# 04_io.net
KiCad netlist of a schematic drawn in Altium Designer
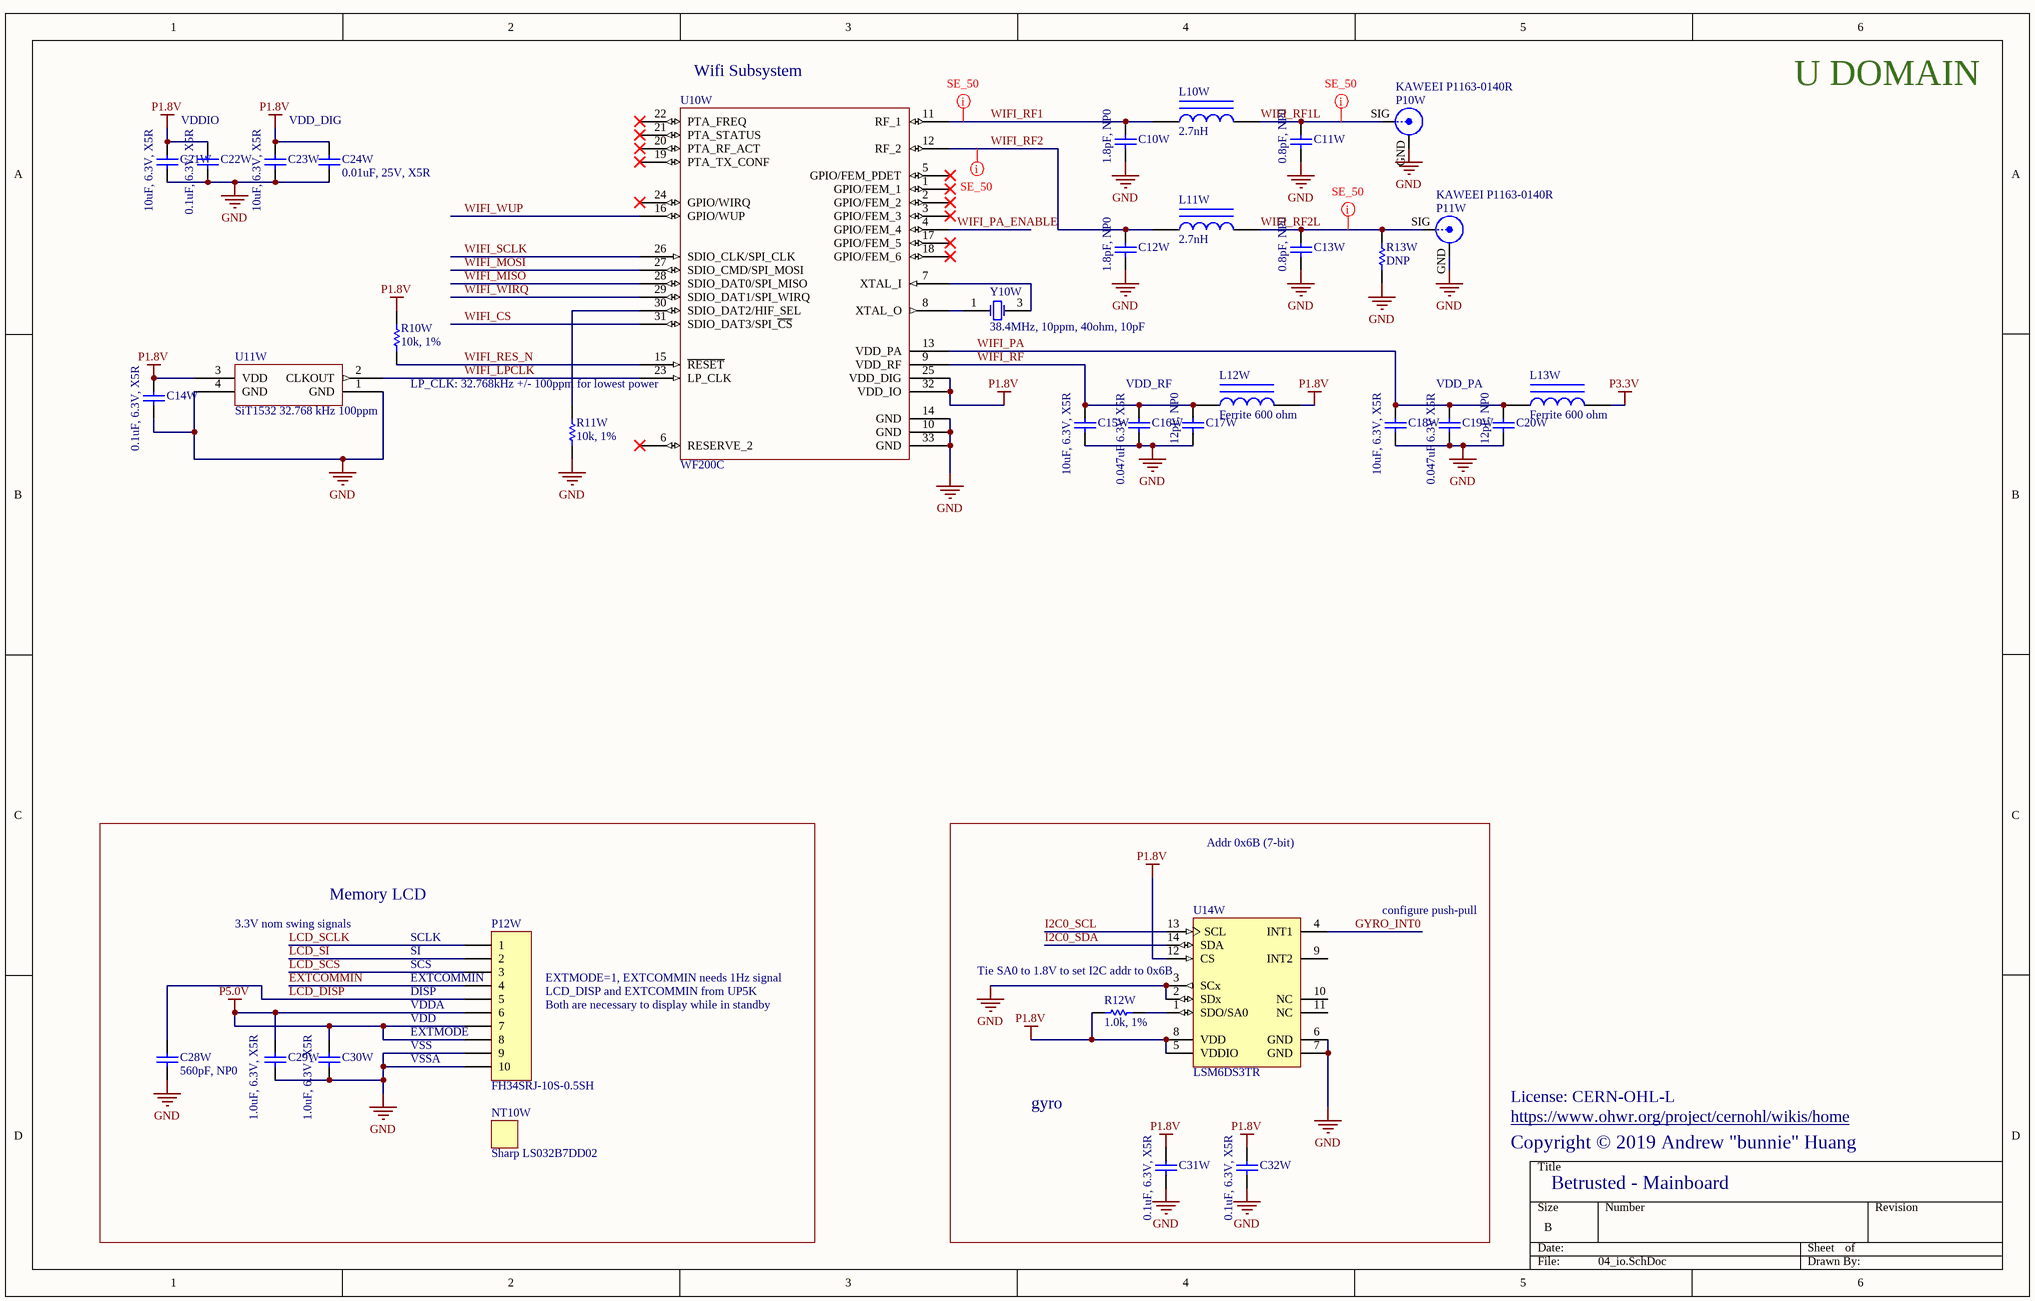
[diagram p0: 04_io.SchDoc]

(export (version "E")
  (design (tool "Eeschema 10.0.6"))
  (components
    (comp (ref "C10W")
      (value "1.8pF, NP0")
      (footprint "B_CAP0201")
      (description "Capacitor (Semiconductor SIM Model)")
      (fields (field (name "MPN") "GRM0335C1H1R8BA01D"))
      (libsource (lib "Miscellaneous Devices") (part "Cap Semi"))
    )
    (comp (ref "C11W")
      (value "0.8pF, NP0")
      (footprint "B_CAP0201")
      (description "Capacitor (Semiconductor SIM Model)")
      (fields (field (name "MPN") "GRM0335C1ER80BA01D"))
      (libsource (lib "Miscellaneous Devices") (part "Cap Semi"))
    )
    (comp (ref "C12W")
      (value "1.8pF, NP0")
      (footprint "B_CAP0201")
      (description "Capacitor (Semiconductor SIM Model)")
      (fields (field (name "MPN") "GRM0335C1H1R8BA01D"))
      (libsource (lib "Miscellaneous Devices") (part "Cap Semi"))
    )
    (comp (ref "C13W")
      (value "0.8pF, NP0")
      (footprint "B_CAP0201")
      (description "Capacitor (Semiconductor SIM Model)")
      (fields (field (name "MPN") "GRM0335C1ER80BA01D"))
      (libsource (lib "Miscellaneous Devices") (part "Cap Semi"))
    )
    (comp (ref "C14W")
      (value "0.1uF, 6.3V, X5R")
      (footprint "B_CAP0201")
      (description "Capacitor (Semiconductor SIM Model)")
      (fields (field (name "MPN") "CL03A104KQ3NNNC"))
      (libsource (lib "Miscellaneous Devices") (part "Cap Semi"))
    )
    (comp (ref "C15W")
      (value "10uF, 6.3V, X5R")
      (footprint "B_CAP0603")
      (description "Capacitor (Semiconductor SIM Model)")
      (fields (field (name "MPN") "CL10A106MQ8NNNC"))
      (libsource (lib "Miscellaneous Devices") (part "Cap Semi"))
    )
    (comp (ref "C16W")
      (value "0.047uF 6.3V X5R")
      (footprint "B_CAP0201")
      (description "Capacitor (Semiconductor SIM Model)")
      (fields (field (name "MPN") "CL03A473KQ3NNNC"))
      (libsource (lib "Miscellaneous Devices") (part "Cap Semi"))
    )
    (comp (ref "C17W")
      (value "12pF, NP0")
      (footprint "B_CAP0201")
      (description "Capacitor (Semiconductor SIM Model)")
      (fields (field (name "MPN") "GRM0335C1E120JA01D"))
      (libsource (lib "Miscellaneous Devices") (part "Cap Semi"))
    )
    (comp (ref "C18W")
      (value "10uF, 6.3V, X5R")
      (footprint "B_CAP0603")
      (description "Capacitor (Semiconductor SIM Model)")
      (fields (field (name "MPN") "CL10A106MQ8NNNC"))
      (libsource (lib "Miscellaneous Devices") (part "Cap Semi"))
    )
    (comp (ref "C19W")
      (value "0.047uF 6.3V X5R")
      (footprint "B_CAP0201")
      (description "Capacitor (Semiconductor SIM Model)")
      (fields (field (name "MPN") "CL03A473KQ3NNNC"))
      (libsource (lib "Miscellaneous Devices") (part "Cap Semi"))
    )
    (comp (ref "C20W")
      (value "12pF, NP0")
      (footprint "B_CAP0201")
      (description "Capacitor (Semiconductor SIM Model)")
      (fields (field (name "MPN") "GRM0335C1E120JA01D"))
      (libsource (lib "Miscellaneous Devices") (part "Cap Semi"))
    )
    (comp (ref "C21W")
      (value "10uF, 6.3V, X5R")
      (footprint "B_CAP0603")
      (description "Capacitor (Semiconductor SIM Model)")
      (fields (field (name "MPN") "CL10A106MQ8NNNC"))
      (libsource (lib "Miscellaneous Devices") (part "Cap Semi"))
    )
    (comp (ref "C22W")
      (value "0.1uF, 6.3V, X5R")
      (footprint "B_CAP0201")
      (description "Capacitor (Semiconductor SIM Model)")
      (fields (field (name "MPN") "CL03A104KQ3NNNC"))
      (libsource (lib "Miscellaneous Devices") (part "Cap Semi"))
    )
    (comp (ref "C23W")
      (value "10uF, 6.3V, X5R")
      (footprint "B_CAP0603")
      (description "Capacitor (Semiconductor SIM Model)")
      (fields (field (name "MPN") "CL10A106MQ8NNNC"))
      (libsource (lib "Miscellaneous Devices") (part "Cap Semi"))
    )
    (comp (ref "C24W")
      (value "0.01uF, 25V, X5R")
      (footprint "B_RES0201")
      (description "Capacitor (Semiconductor SIM Model)")
      (fields (field (name "MPN") "GRM033R61E103KA12D"))
      (libsource (lib "Miscellaneous Devices") (part "Cap Semi"))
    )
    (comp (ref "C28W")
      (value "560pF, NP0")
      (footprint "B_RES0201")
      (description "Capacitor (Semiconductor SIM Model)")
      (fields (field (name "MPN") "GRM0335C1E561JA01D"))
      (libsource (lib "Miscellaneous Devices") (part "Cap Semi"))
    )
    (comp (ref "C29W")
      (value "1.0uF, 6.3V, X5R")
      (footprint "B_CAP0201")
      (description "Capacitor (Semiconductor SIM Model)")
      (fields (field (name "MPN") "GRM033R60J105MEA2D"))
      (libsource (lib "Miscellaneous Devices") (part "Cap Semi"))
    )
    (comp (ref "C30W")
      (value "1.0uF, 6.3V, X5R")
      (footprint "B_CAP0201")
      (description "Capacitor (Semiconductor SIM Model)")
      (fields (field (name "MPN") "GRM033R60J105MEA2D"))
      (libsource (lib "Miscellaneous Devices") (part "Cap Semi"))
    )
    (comp (ref "C31W")
      (value "0.1uF, 6.3V, X5R")
      (footprint "B_CAP0201")
      (description "Capacitor (Semiconductor SIM Model)")
      (fields (field (name "MPN") "CL03A104KQ3NNNC"))
      (libsource (lib "Miscellaneous Devices") (part "Cap Semi"))
    )
    (comp (ref "C32W")
      (value "0.1uF, 6.3V, X5R")
      (footprint "B_CAP0201")
      (description "Capacitor (Semiconductor SIM Model)")
      (fields (field (name "MPN") "CL03A104KQ3NNNC"))
      (libsource (lib "Miscellaneous Devices") (part "Cap Semi"))
    )
    (comp (ref "L10W")
      (value "2.7nH")
      (footprint "B_IND0402")
      (description "Magnetic-Core Inductor")
      (fields (field (name "MPN") "LQW15AN2N7C00"))
      (libsource (lib "Miscellaneous Devices") (part "Inductor Iron"))
    )
    (comp (ref "L11W")
      (value "2.7nH")
      (footprint "B_IND0402")
      (description "Magnetic-Core Inductor")
      (fields (field (name "MPN") "LQW15AN2N7C00"))
      (libsource (lib "Miscellaneous Devices") (part "Inductor Iron"))
    )
    (comp (ref "L12W")
      (value "Ferrite 600 ohm")
      (footprint "B_IND0603")
      (description "Magnetic-Core Inductor")
      (fields (field (name "MPN") "BLM18AG601SN1D"))
      (libsource (lib "Miscellaneous Devices") (part "Inductor Iron"))
    )
    (comp (ref "L13W")
      (value "Ferrite 600 ohm")
      (footprint "B_IND0603")
      (description "Magnetic-Core Inductor")
      (fields (field (name "MPN") "BLM18AG601SN1D"))
      (libsource (lib "Miscellaneous Devices") (part "Inductor Iron"))
    )
    (comp (ref "NT10W")
      (value "Sharp LS032B7DD02")
      (description "Placeholder for non-board BOM items")
      (fields (field (name "MPN") "LS032B7DD02"))
      (libsource (lib "commonsch") (part "NOTE"))
    )
    (comp (ref "P10W")
      (value "KAWEEI P1163-0140R")
      (footprint "HRS_U.FL")
      (description "BNC Elbow Connector")
      (fields (field (name "MPN") "P1163-0140R") (field (name "PUBLISHER") "Altium Limited"))
      (libsource (lib "Miscellaneous Connectors") (part "BNC"))
    )
    (comp (ref "P11W")
      (value "KAWEEI P1163-0140R")
      (footprint "HRS_U.FL")
      (description "BNC Elbow Connector")
      (fields (field (name "MPN") "P1163-0140R") (field (name "PUBLISHER") "Altium Limited"))
      (libsource (lib "Miscellaneous Connectors") (part "BNC"))
    )
    (comp (ref "P12W")
      (value "FH34SRJ-10S-0.5SH")
      (footprint "HRS_FH34SRJ-10S-0.5SH(50)")
      (description "Header, 10-Pin")
      (fields (field (name "PUBLISHER") "Altium Limited"))
      (libsource (lib "Miscellaneous Connectors") (part "Header 10"))
    )
    (comp (ref "R10W")
      (value "10k, 1%")
      (footprint "B_RES0201")
      (description "Resistor")
      (fields (field (name "MPN") "ANY"))
      (libsource (lib "Miscellaneous Devices") (part "Res1"))
    )
    (comp (ref "R11W")
      (value "10k, 1%")
      (footprint "B_RES0201")
      (description "Resistor")
      (fields (field (name "MPN") "ANY"))
      (libsource (lib "Miscellaneous Devices") (part "Res1"))
    )
    (comp (ref "R12W")
      (value "1.0k, 1%")
      (footprint "B_RES0201")
      (description "Resistor")
      (fields (field (name "MPN") "ANY"))
      (libsource (lib "Miscellaneous Devices") (part "Res1"))
    )
    (comp (ref "R13W")
      (value "DNP")
      (footprint "B_RES0201")
      (description "Resistor")
      (libsource (lib "Miscellaneous Devices") (part "Res1"))
    )
    (comp (ref "U10W")
      (value "WF200C")
      (footprint "QFN40P400X400X90_HS-33N")
      (description "Wifi Network Coprocessor")
      (libsource (lib "commonsch-new") (part "WF200C(R)"))
    )
    (comp (ref "U11W")
      (value "SiT1532 32.768 kHz 100ppm")
      (footprint "SiTIME_CSP")
      (description "10ppm ultra low power 32.768 kHz replacement")
      (fields (field (name "MPN") "SIT1532AI-J4-DCC-32.768E"))
      (libsource (lib "altium-import") (part "root_2_SiT1532_"))
    )
    (comp (ref "U14W")
      (value "LSM6DS3TR")
      (footprint "LGA-14_2500X3000X860_N")
      (libsource (lib "commonsch-new") (part "LSM6DS3TR"))
    )
    (comp (ref "Y10W")
      (value "38.4MHz, 10ppm, 40ohm, 10pF")
      (footprint "XOSC_3.2_2.5")
      (description "Crystal Oscillator")
      (fields (field (name "MPN") "ECS-384-10-33B-CKY-TR") (field (name "PUBLISHER") "Altium Limited"))
      (libsource (lib "Miscellaneous Devices") (part "XTAL"))
    )
  )
  (nets
    (net (code "1") (name "/EXTCOMMIN") (class "Default")
      (node (ref "P12W") (pin "4") (pinfunction "4_4") (pintype "passive"))
    )
    (net (code "2") (name "/GYRO_INT0") (class "Default")
      (node (ref "U14W") (pin "4") (pinfunction "INT1_4") (pintype "open_collector"))
    )
    (net (code "3") (name "/I2C0_SCL") (class "Default")
      (node (ref "U14W") (pin "13") (pinfunction "SCL_13") (pintype "input"))
    )
    (net (code "4") (name "/I2C0_SDA") (class "Default")
      (node (ref "U14W") (pin "14") (pinfunction "SDA_14") (pintype "bidirectional"))
    )
    (net (code "5") (name "/LCD_DISP") (class "Default")
      (node (ref "C28W") (pin "1") (pinfunction "1_1") (pintype "passive"))
      (node (ref "P12W") (pin "5") (pinfunction "5_5") (pintype "passive"))
    )
    (net (code "6") (name "/LCD_SCLK") (class "Default")
      (node (ref "P12W") (pin "1") (pinfunction "1_1") (pintype "passive"))
    )
    (net (code "7") (name "/LCD_SCS") (class "Default")
      (node (ref "P12W") (pin "3") (pinfunction "3_3") (pintype "passive"))
    )
    (net (code "8") (name "/LCD_SI") (class "Default")
      (node (ref "P12W") (pin "2") (pinfunction "2_2") (pintype "passive"))
    )
    (net (code "9") (name "/WIFI_CS") (class "Default")
      (node (ref "U10W") (pin "31") (pinfunction "SDIO_DAT3/SPI_~{CS}_31") (pintype "bidirectional"))
    )
    (net (code "10") (name "/WIFI_LPCLK") (class "Default")
      (node (ref "U10W") (pin "23") (pinfunction "LP_CLK_23") (pintype "input"))
      (node (ref "U11W") (pin "2") (pinfunction "CLKOUT_2") (pintype "output"))
    )
    (net (code "11") (name "/WIFI_MISO") (class "Default")
      (node (ref "U10W") (pin "28") (pinfunction "SDIO_DAT0/SPI_MISO_28") (pintype "bidirectional"))
    )
    (net (code "12") (name "/WIFI_MOSI") (class "Default")
      (node (ref "U10W") (pin "27") (pinfunction "SDIO_CMD/SPI_MOSI_27") (pintype "bidirectional"))
    )
    (net (code "13") (name "/WIFI_PA") (class "Default")
      (node (ref "C18W") (pin "1") (pinfunction "1_1") (pintype "passive"))
      (node (ref "C19W") (pin "1") (pinfunction "1_1") (pintype "passive"))
      (node (ref "C20W") (pin "1") (pinfunction "1_1") (pintype "passive"))
      (node (ref "L13W") (pin "1") (pinfunction "1_1") (pintype "passive"))
      (node (ref "U10W") (pin "13") (pinfunction "VDD_PA_13") (pintype "power_in"))
    )
    (net (code "14") (name "/WIFI_PA_ENABLE") (class "Default")
      (node (ref "U10W") (pin "4") (pinfunction "GPIO/FEM_4_4") (pintype "bidirectional"))
    )
    (net (code "15") (name "/WIFI_RES_N") (class "Default")
      (node (ref "R10W") (pin "2") (pinfunction "2_2") (pintype "passive"))
      (node (ref "U10W") (pin "15") (pinfunction "~{RESET}_15") (pintype "input"))
    )
    (net (code "16") (name "/WIFI_RF") (class "Default")
      (node (ref "C15W") (pin "1") (pinfunction "1_1") (pintype "passive"))
      (node (ref "C16W") (pin "1") (pinfunction "1_1") (pintype "passive"))
      (node (ref "C17W") (pin "1") (pinfunction "1_1") (pintype "passive"))
      (node (ref "L12W") (pin "1") (pinfunction "1_1") (pintype "passive"))
      (node (ref "U10W") (pin "9") (pinfunction "VDD_RF_9") (pintype "power_in"))
    )
    (net (code "17") (name "/WIFI_RF1") (class "Default")
      (node (ref "C10W") (pin "1") (pinfunction "1_1") (pintype "passive"))
      (node (ref "L10W") (pin "1") (pinfunction "1_1") (pintype "passive"))
      (node (ref "U10W") (pin "11") (pinfunction "RF_1_11") (pintype "bidirectional"))
    )
    (net (code "18") (name "/WIFI_RF1L") (class "Default")
      (node (ref "C11W") (pin "1") (pinfunction "1_1") (pintype "passive"))
      (node (ref "L10W") (pin "2") (pinfunction "2_2") (pintype "passive"))
      (node (ref "P10W") (pin "SIG") (pinfunction "X_SIG") (pintype "passive"))
    )
    (net (code "19") (name "/WIFI_RF2") (class "Default")
      (node (ref "C12W") (pin "1") (pinfunction "1_1") (pintype "passive"))
      (node (ref "L11W") (pin "1") (pinfunction "1_1") (pintype "passive"))
      (node (ref "U10W") (pin "12") (pinfunction "RF_2_12") (pintype "bidirectional"))
    )
    (net (code "20") (name "/WIFI_RF2L") (class "Default")
      (node (ref "C13W") (pin "1") (pinfunction "1_1") (pintype "passive"))
      (node (ref "L11W") (pin "2") (pinfunction "2_2") (pintype "passive"))
      (node (ref "P11W") (pin "SIG") (pinfunction "X_SIG") (pintype "passive"))
      (node (ref "R13W") (pin "1") (pinfunction "1_1") (pintype "passive"))
    )
    (net (code "21") (name "/WIFI_SCLK") (class "Default")
      (node (ref "U10W") (pin "26") (pinfunction "SDIO_CLK/SPI_CLK_26") (pintype "input"))
    )
    (net (code "22") (name "/WIFI_WIRQ") (class "Default")
      (node (ref "U10W") (pin "29") (pinfunction "SDIO_DAT1/SPI_WIRQ_29") (pintype "bidirectional"))
    )
    (net (code "23") (name "/WIFI_WUP") (class "Default")
      (node (ref "U10W") (pin "16") (pinfunction "GPIO/WUP_16") (pintype "bidirectional"))
    )
    (net (code "24") (name "GND") (class "Default")
      (node (ref "C10W") (pin "2") (pinfunction "2_2") (pintype "passive"))
      (node (ref "C11W") (pin "2") (pinfunction "2_2") (pintype "passive"))
      (node (ref "C12W") (pin "2") (pinfunction "2_2") (pintype "passive"))
      (node (ref "C13W") (pin "2") (pinfunction "2_2") (pintype "passive"))
      (node (ref "C14W") (pin "2") (pinfunction "2_2") (pintype "passive"))
      (node (ref "C15W") (pin "2") (pinfunction "2_2") (pintype "passive"))
      (node (ref "C16W") (pin "2") (pinfunction "2_2") (pintype "passive"))
      (node (ref "C17W") (pin "2") (pinfunction "2_2") (pintype "passive"))
      (node (ref "C18W") (pin "2") (pinfunction "2_2") (pintype "passive"))
      (node (ref "C19W") (pin "2") (pinfunction "2_2") (pintype "passive"))
      (node (ref "C20W") (pin "2") (pinfunction "2_2") (pintype "passive"))
      (node (ref "C21W") (pin "2") (pinfunction "2_2") (pintype "passive"))
      (node (ref "C22W") (pin "2") (pinfunction "2_2") (pintype "passive"))
      (node (ref "C23W") (pin "2") (pinfunction "2_2") (pintype "passive"))
      (node (ref "C24W") (pin "2") (pinfunction "2_2") (pintype "passive"))
      (node (ref "C28W") (pin "2") (pinfunction "2_2") (pintype "passive"))
      (node (ref "C29W") (pin "1") (pinfunction "1_1") (pintype "passive"))
      (node (ref "C30W") (pin "1") (pinfunction "1_1") (pintype "passive"))
      (node (ref "C31W") (pin "2") (pinfunction "2_2") (pintype "passive"))
      (node (ref "C32W") (pin "2") (pinfunction "2_2") (pintype "passive"))
      (node (ref "P10W") (pin "GND") (pinfunction "Y_GND") (pintype "passive"))
      (node (ref "P11W") (pin "GND") (pinfunction "Y_GND") (pintype "passive"))
      (node (ref "P12W") (pin "10") (pinfunction "10_10") (pintype "passive"))
      (node (ref "P12W") (pin "9") (pinfunction "9_9") (pintype "passive"))
      (node (ref "R11W") (pin "2") (pinfunction "2_2") (pintype "passive"))
      (node (ref "R13W") (pin "2") (pinfunction "2_2") (pintype "passive"))
      (node (ref "U10W") (pin "10") (pinfunction "GND_10") (pintype "power_in"))
      (node (ref "U10W") (pin "14") (pinfunction "GND_14") (pintype "power_in"))
      (node (ref "U10W") (pin "33") (pinfunction "GND_33") (pintype "power_in"))
      (node (ref "U11W") (pin "1") (pinfunction "GND_1") (pintype "power_in"))
      (node (ref "U11W") (pin "4") (pinfunction "GND_4") (pintype "power_in"))
      (node (ref "U14W") (pin "2") (pinfunction "SDx_2") (pintype "bidirectional"))
      (node (ref "U14W") (pin "3") (pinfunction "SCx_3") (pintype "output"))
      (node (ref "U14W") (pin "6") (pinfunction "GND_6") (pintype "power_in"))
      (node (ref "U14W") (pin "7") (pinfunction "GND_7") (pintype "power_in"))
    )
    (net (code "25") (name "Net-(U10W-SDIO_DAT2{slash}HIF_SEL)") (class "Default")
      (node (ref "R11W") (pin "1") (pinfunction "1_1") (pintype "passive"))
      (node (ref "U10W") (pin "30") (pinfunction "SDIO_DAT2/HIF_SEL_30") (pintype "bidirectional"))
    )
    (net (code "26") (name "Net-(U10W-XTAL_I)") (class "Default")
      (node (ref "U10W") (pin "7") (pinfunction "XTAL_I_7") (pintype "input"))
      (node (ref "Y10W") (pin "3") (pinfunction "OSC2_3") (pintype "passive"))
    )
    (net (code "27") (name "Net-(U10W-XTAL_O)") (class "Default")
      (node (ref "U10W") (pin "8") (pinfunction "XTAL_O_8") (pintype "output"))
      (node (ref "Y10W") (pin "1") (pinfunction "OSC1_1") (pintype "passive"))
    )
    (net (code "28") (name "Net-(U14W-SDO{slash}SA0)") (class "Default")
      (node (ref "R12W") (pin "1") (pinfunction "1_1") (pintype "passive"))
      (node (ref "U14W") (pin "1") (pinfunction "SDO/SA0_1") (pintype "bidirectional"))
    )
    (net (code "29") (name "P1.8V") (class "Default")
      (node (ref "C14W") (pin "1") (pinfunction "1_1") (pintype "passive"))
      (node (ref "C21W") (pin "1") (pinfunction "1_1") (pintype "passive"))
      (node (ref "C22W") (pin "1") (pinfunction "1_1") (pintype "passive"))
      (node (ref "C23W") (pin "1") (pinfunction "1_1") (pintype "passive"))
      (node (ref "C24W") (pin "1") (pinfunction "1_1") (pintype "passive"))
      (node (ref "C31W") (pin "1") (pinfunction "1_1") (pintype "passive"))
      (node (ref "C32W") (pin "1") (pinfunction "1_1") (pintype "passive"))
      (node (ref "L12W") (pin "2") (pinfunction "2_2") (pintype "passive"))
      (node (ref "R10W") (pin "1") (pinfunction "1_1") (pintype "passive"))
      (node (ref "R12W") (pin "2") (pinfunction "2_2") (pintype "passive"))
      (node (ref "U10W") (pin "25") (pinfunction "VDD_DIG_25") (pintype "power_in"))
      (node (ref "U10W") (pin "32") (pinfunction "VDD_IO_32") (pintype "power_in"))
      (node (ref "U11W") (pin "3") (pinfunction "VDD_3") (pintype "power_in"))
      (node (ref "U14W") (pin "12") (pinfunction "CS_12") (pintype "input"))
      (node (ref "U14W") (pin "5") (pinfunction "VDDIO_5") (pintype "power_in"))
      (node (ref "U14W") (pin "8") (pinfunction "VDD_8") (pintype "power_in"))
    )
    (net (code "30") (name "P3.3V") (class "Default")
      (node (ref "L13W") (pin "2") (pinfunction "2_2") (pintype "passive"))
    )
    (net (code "31") (name "P5.0V") (class "Default")
      (node (ref "C29W") (pin "2") (pinfunction "2_2") (pintype "passive"))
      (node (ref "C30W") (pin "2") (pinfunction "2_2") (pintype "passive"))
      (node (ref "P12W") (pin "6") (pinfunction "6_6") (pintype "passive"))
      (node (ref "P12W") (pin "7") (pinfunction "7_7") (pintype "passive"))
      (node (ref "P12W") (pin "8") (pinfunction "8_8") (pintype "passive"))
    )
    (net (code "32") (name "unconnected-(U10W-GPIO{slash}FEM_1-Pad1)") (class "Default")
      (node (ref "U10W") (pin "1") (pinfunction "GPIO/FEM_1_1") (pintype "bidirectional+no_connect"))
    )
    (net (code "33") (name "unconnected-(U10W-GPIO{slash}FEM_2-Pad2)") (class "Default")
      (node (ref "U10W") (pin "2") (pinfunction "GPIO/FEM_2_2") (pintype "bidirectional+no_connect"))
    )
    (net (code "34") (name "unconnected-(U10W-GPIO{slash}FEM_3-Pad3)") (class "Default")
      (node (ref "U10W") (pin "3") (pinfunction "GPIO/FEM_3_3") (pintype "bidirectional+no_connect"))
    )
    (net (code "35") (name "unconnected-(U10W-GPIO{slash}FEM_5-Pad17)") (class "Default")
      (node (ref "U10W") (pin "17") (pinfunction "GPIO/FEM_5_17") (pintype "bidirectional+no_connect"))
    )
    (net (code "36") (name "unconnected-(U10W-GPIO{slash}FEM_6-Pad18)") (class "Default")
      (node (ref "U10W") (pin "18") (pinfunction "GPIO/FEM_6_18") (pintype "bidirectional+no_connect"))
    )
    (net (code "37") (name "unconnected-(U10W-GPIO{slash}FEM_PDET-Pad5)") (class "Default")
      (node (ref "U10W") (pin "5") (pinfunction "GPIO/FEM_PDET_5") (pintype "bidirectional+no_connect"))
    )
    (net (code "38") (name "unconnected-(U10W-GPIO{slash}WIRQ-Pad24)") (class "Default")
      (node (ref "U10W") (pin "24") (pinfunction "GPIO/WIRQ_24") (pintype "bidirectional+no_connect"))
    )
    (net (code "39") (name "unconnected-(U10W-PTA_FREQ-Pad22)") (class "Default")
      (node (ref "U10W") (pin "22") (pinfunction "PTA_FREQ_22") (pintype "bidirectional+no_connect"))
    )
    (net (code "40") (name "unconnected-(U10W-PTA_RF_ACT-Pad20)") (class "Default")
      (node (ref "U10W") (pin "20") (pinfunction "PTA_RF_ACT_20") (pintype "bidirectional+no_connect"))
    )
    (net (code "41") (name "unconnected-(U10W-PTA_STATUS-Pad21)") (class "Default")
      (node (ref "U10W") (pin "21") (pinfunction "PTA_STATUS_21") (pintype "bidirectional+no_connect"))
    )
    (net (code "42") (name "unconnected-(U10W-PTA_TX_CONF-Pad19)") (class "Default")
      (node (ref "U10W") (pin "19") (pinfunction "PTA_TX_CONF_19") (pintype "bidirectional+no_connect"))
    )
    (net (code "43") (name "unconnected-(U10W-RESERVE_2-Pad6)") (class "Default")
      (node (ref "U10W") (pin "6") (pinfunction "RESERVE_2_6") (pintype "bidirectional+no_connect"))
    )
    (net (code "44") (name "unconnected-(U14W-INT2-Pad9)") (class "Default")
      (node (ref "U14W") (pin "9") (pinfunction "INT2_9") (pintype "open_collector"))
    )
    (net (code "45") (name "unconnected-(U14W-NC-Pad10)") (class "Default")
      (node (ref "U14W") (pin "10") (pinfunction "NC_10") (pintype "passive"))
    )
    (net (code "46") (name "unconnected-(U14W-NC-Pad11)") (class "Default")
      (node (ref "U14W") (pin "11") (pinfunction "NC_11") (pintype "passive"))
    )
  )
)
